# kitt.net
KiCad netlist of a schematic drawn in EAGLE
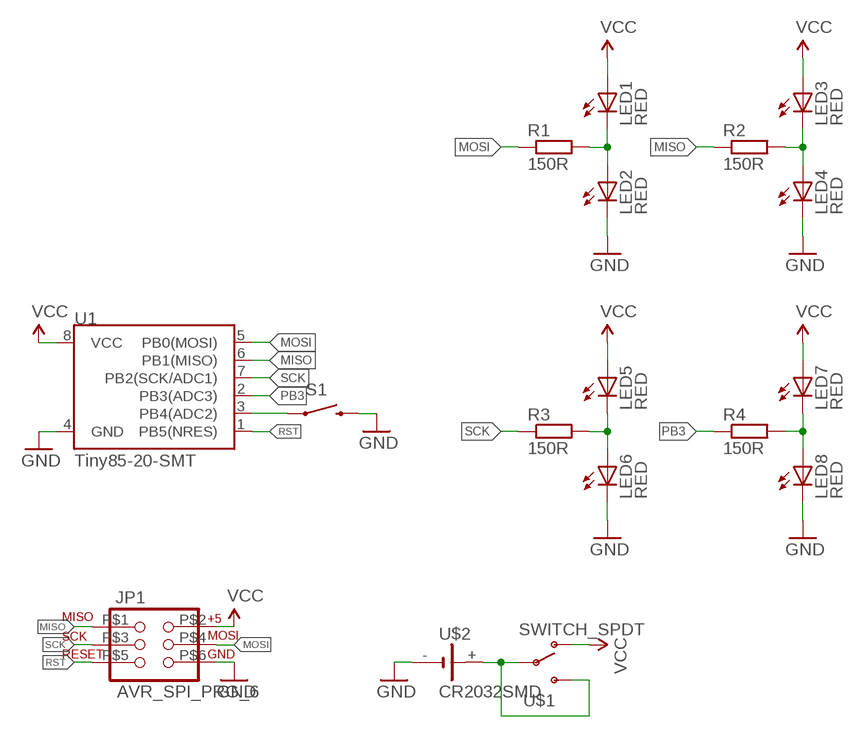
[diagram p0: schematic, sheet 1]

(export (version "E")
  (design (tool "Eeschema 10.0.6"))
  (components
    (comp (ref "JP1")
      (value "AVR_SPI_PRG_6")
      (footprint "eagle-import:2X3_SMD_PAD")
      (libsource (lib "eagle-import") (part "AVR_SPI_PRG_6"))
    )
    (comp (ref "LED1")
      (value "RED")
      (footprint "eagle-import:CHIP-LED0805")
      (libsource (lib "eagle-import") (part "LEDCHIP-LED0805"))
    )
    (comp (ref "LED2")
      (value "RED")
      (footprint "eagle-import:CHIP-LED0805")
      (libsource (lib "eagle-import") (part "LEDCHIP-LED0805"))
    )
    (comp (ref "LED3")
      (value "RED")
      (footprint "eagle-import:CHIP-LED0805")
      (libsource (lib "eagle-import") (part "LEDCHIP-LED0805"))
    )
    (comp (ref "LED4")
      (value "RED")
      (footprint "eagle-import:CHIP-LED0805")
      (libsource (lib "eagle-import") (part "LEDCHIP-LED0805"))
    )
    (comp (ref "LED5")
      (value "RED")
      (footprint "eagle-import:CHIP-LED0805")
      (libsource (lib "eagle-import") (part "LEDCHIP-LED0805"))
    )
    (comp (ref "LED6")
      (value "RED")
      (footprint "eagle-import:CHIP-LED0805")
      (libsource (lib "eagle-import") (part "LEDCHIP-LED0805"))
    )
    (comp (ref "LED7")
      (value "RED")
      (footprint "eagle-import:CHIP-LED0805")
      (libsource (lib "eagle-import") (part "LEDCHIP-LED0805"))
    )
    (comp (ref "LED8")
      (value "RED")
      (footprint "eagle-import:CHIP-LED0805")
      (libsource (lib "eagle-import") (part "LEDCHIP-LED0805"))
    )
    (comp (ref "R1")
      (value "150R")
      (footprint "eagle-import:M0805")
      (libsource (lib "eagle-import") (part "R-EU_M0805"))
    )
    (comp (ref "R2")
      (value "150R")
      (footprint "eagle-import:M0805")
      (libsource (lib "eagle-import") (part "R-EU_M0805"))
    )
    (comp (ref "R3")
      (value "150R")
      (footprint "eagle-import:M0805")
      (libsource (lib "eagle-import") (part "R-EU_M0805"))
    )
    (comp (ref "R4")
      (value "150R")
      (footprint "eagle-import:M0805")
      (libsource (lib "eagle-import") (part "R-EU_M0805"))
    )
    (comp (ref "S1")
      (value "SWITCH-MOMENTARY-2-SMD-1101NE")
      (footprint "eagle-import:TACTILE-SWITCH-1101NE")
      (libsource (lib "eagle-import") (part "SWITCH-MOMENTARY-2-SMD-1101NE"))
    )
    (comp (ref "U$1")
      (value "SWITCH_SPDT")
      (footprint "eagle-import:KPS-1290")
      (libsource (lib "eagle-import") (part "SWITCH_SPDT"))
    )
    (comp (ref "U$2")
      (value "CR2032SMD")
      (footprint "eagle-import:CR2032SMD")
      (libsource (lib "eagle-import") (part "CR2032SMD"))
    )
    (comp (ref "U1")
      (value "Tiny85-20-SMT")
      (footprint "eagle-import:SO08-EIAJ")
      (libsource (lib "eagle-import") (part "ATTINY45TINY85-20-SMT"))
    )
  )
  (nets
    (net (code "1") (name "GND") (class "Default")
      (node (ref "JP1") (pin "P$6") (pinfunction "6_P$6") (pintype "passive"))
      (node (ref "LED2") (pin "C") (pinfunction "C_C") (pintype "passive"))
      (node (ref "LED4") (pin "C") (pinfunction "C_C") (pintype "passive"))
      (node (ref "LED6") (pin "C") (pinfunction "C_C") (pintype "passive"))
      (node (ref "LED8") (pin "C") (pinfunction "C_C") (pintype "passive"))
      (node (ref "S1") (pin "P$2") (pinfunction "2_P$2") (pintype "passive"))
      (node (ref "U$2") (pin "-") (pinfunction "-_-") (pintype "passive"))
      (node (ref "U1") (pin "4") (pinfunction "GND_4") (pintype "bidirectional"))
    )
    (net (code "2") (name "MISO") (class "Default")
      (node (ref "JP1") (pin "P$1") (pinfunction "1_P$1") (pintype "passive"))
      (node (ref "R2") (pin "1") (pinfunction "1_1") (pintype "passive"))
      (node (ref "U1") (pin "6") (pinfunction "PB1(MISO)_6") (pintype "bidirectional"))
    )
    (net (code "3") (name "MOSI") (class "Default")
      (node (ref "JP1") (pin "P$4") (pinfunction "4_P$4") (pintype "passive"))
      (node (ref "R1") (pin "1") (pinfunction "1_1") (pintype "passive"))
      (node (ref "U1") (pin "5") (pinfunction "PB0(MOSI)_5") (pintype "bidirectional"))
    )
    (net (code "4") (name "Net-(LED1-PadC)") (class "Default")
      (node (ref "LED1") (pin "C") (pinfunction "C_C") (pintype "passive"))
      (node (ref "LED2") (pin "A") (pinfunction "A_A") (pintype "passive"))
      (node (ref "R1") (pin "2") (pinfunction "2_2") (pintype "passive"))
    )
    (net (code "5") (name "Net-(LED3-PadC)") (class "Default")
      (node (ref "LED3") (pin "C") (pinfunction "C_C") (pintype "passive"))
      (node (ref "LED4") (pin "A") (pinfunction "A_A") (pintype "passive"))
      (node (ref "R2") (pin "2") (pinfunction "2_2") (pintype "passive"))
    )
    (net (code "6") (name "Net-(LED5-PadC)") (class "Default")
      (node (ref "LED5") (pin "C") (pinfunction "C_C") (pintype "passive"))
      (node (ref "LED6") (pin "A") (pinfunction "A_A") (pintype "passive"))
      (node (ref "R3") (pin "2") (pinfunction "2_2") (pintype "passive"))
    )
    (net (code "7") (name "Net-(LED7-PadC)") (class "Default")
      (node (ref "LED7") (pin "C") (pinfunction "C_C") (pintype "passive"))
      (node (ref "LED8") (pin "A") (pinfunction "A_A") (pintype "passive"))
      (node (ref "R4") (pin "2") (pinfunction "2_2") (pintype "passive"))
    )
    (net (code "8") (name "Net-(S1-1)") (class "Default")
      (node (ref "S1") (pin "P$1") (pinfunction "1_P$1") (pintype "passive"))
      (node (ref "U1") (pin "3") (pinfunction "PB4(ADC2)_3") (pintype "bidirectional"))
    )
    (net (code "9") (name "Net-(U$1-PadP)") (class "Default")
      (node (ref "U$1") (pin "P") (pinfunction "P_P") (pintype "passive"))
      (node (ref "U$1") (pin "S") (pinfunction "S_S") (pintype "passive"))
      (node (ref "U$2") (pin "+") (pinfunction "+_+") (pintype "passive"))
    )
    (net (code "10") (name "PB3") (class "Default")
      (node (ref "R4") (pin "1") (pinfunction "1_1") (pintype "passive"))
      (node (ref "U1") (pin "2") (pinfunction "PB3(ADC3)_2") (pintype "bidirectional"))
    )
    (net (code "11") (name "RST") (class "Default")
      (node (ref "JP1") (pin "P$5") (pinfunction "5_P$5") (pintype "passive"))
      (node (ref "U1") (pin "1") (pinfunction "PB5(NRES)_1") (pintype "bidirectional"))
    )
    (net (code "12") (name "SCK") (class "Default")
      (node (ref "JP1") (pin "P$3") (pinfunction "3_P$3") (pintype "passive"))
      (node (ref "R3") (pin "1") (pinfunction "1_1") (pintype "passive"))
      (node (ref "U1") (pin "7") (pinfunction "PB2(SCK/ADC1)_7") (pintype "bidirectional"))
    )
    (net (code "13") (name "VCC") (class "Default")
      (node (ref "JP1") (pin "P$2") (pinfunction "2_P$2") (pintype "passive"))
      (node (ref "LED1") (pin "A") (pinfunction "A_A") (pintype "passive"))
      (node (ref "LED3") (pin "A") (pinfunction "A_A") (pintype "passive"))
      (node (ref "LED5") (pin "A") (pinfunction "A_A") (pintype "passive"))
      (node (ref "LED7") (pin "A") (pinfunction "A_A") (pintype "passive"))
      (node (ref "U$1") (pin "O") (pinfunction "O_O") (pintype "passive"))
      (node (ref "U1") (pin "8") (pinfunction "VCC_8") (pintype "bidirectional"))
    )
  )
)
